# sheet4_sk6812.net
KiCad netlist of a schematic drawn in Altium Designer
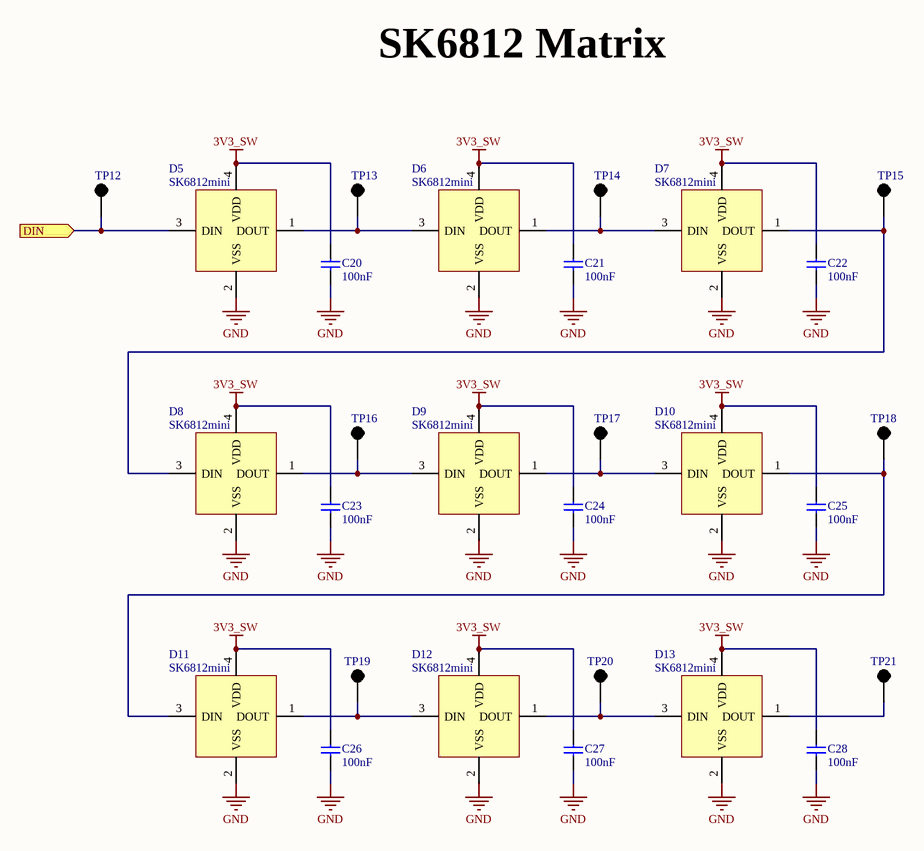
[diagram p0: sheet4_sk6812.SchDoc]

(export (version "E")
  (design (tool "Eeschema 10.0.6"))
  (components
    (comp (ref "C20")
      (value "100nF")
      (footprint "CAP0603_GCx18_MURATA")
      (description "Capacitor 0603 100nF")
      (fields
        (field (name "MANUFACTURER") "Murata")
        (field (name "MANUFACTURER PART NUMBER") "GCJ188R71C104KA01D")
      )
      (libsource (lib "Schlib") (part "CAP_0603_100nF"))
    )
    (comp (ref "C21")
      (value "100nF")
      (footprint "CAP0603_GCx18_MURATA")
      (description "Capacitor 0603 100nF")
      (fields
        (field (name "MANUFACTURER") "Murata")
        (field (name "MANUFACTURER PART NUMBER") "GCJ188R71C104KA01D")
      )
      (libsource (lib "Schlib") (part "CAP_0603_100nF"))
    )
    (comp (ref "C22")
      (value "100nF")
      (footprint "CAP0603_GCx18_MURATA")
      (description "Capacitor 0603 100nF")
      (fields
        (field (name "MANUFACTURER") "Murata")
        (field (name "MANUFACTURER PART NUMBER") "GCJ188R71C104KA01D")
      )
      (libsource (lib "Schlib") (part "CAP_0603_100nF"))
    )
    (comp (ref "C23")
      (value "100nF")
      (footprint "CAP0603_GCx18_MURATA")
      (description "Capacitor 0603 100nF")
      (fields
        (field (name "MANUFACTURER") "Murata")
        (field (name "MANUFACTURER PART NUMBER") "GCJ188R71C104KA01D")
      )
      (libsource (lib "Schlib") (part "CAP_0603_100nF"))
    )
    (comp (ref "C24")
      (value "100nF")
      (footprint "CAP0603_GCx18_MURATA")
      (description "Capacitor 0603 100nF")
      (fields
        (field (name "MANUFACTURER") "Murata")
        (field (name "MANUFACTURER PART NUMBER") "GCJ188R71C104KA01D")
      )
      (libsource (lib "Schlib") (part "CAP_0603_100nF"))
    )
    (comp (ref "C25")
      (value "100nF")
      (footprint "CAP0603_GCx18_MURATA")
      (description "Capacitor 0603 100nF")
      (fields
        (field (name "MANUFACTURER") "Murata")
        (field (name "MANUFACTURER PART NUMBER") "GCJ188R71C104KA01D")
      )
      (libsource (lib "Schlib") (part "CAP_0603_100nF"))
    )
    (comp (ref "C26")
      (value "100nF")
      (footprint "CAP0603_GCx18_MURATA")
      (description "Capacitor 0603 100nF")
      (fields
        (field (name "MANUFACTURER") "Murata")
        (field (name "MANUFACTURER PART NUMBER") "GCJ188R71C104KA01D")
      )
      (libsource (lib "Schlib") (part "CAP_0603_100nF"))
    )
    (comp (ref "C27")
      (value "100nF")
      (footprint "CAP0603_GCx18_MURATA")
      (description "Capacitor 0603 100nF")
      (fields
        (field (name "MANUFACTURER") "Murata")
        (field (name "MANUFACTURER PART NUMBER") "GCJ188R71C104KA01D")
      )
      (libsource (lib "Schlib") (part "CAP_0603_100nF"))
    )
    (comp (ref "C28")
      (value "100nF")
      (footprint "CAP0603_GCx18_MURATA")
      (description "Capacitor 0603 100nF")
      (fields
        (field (name "MANUFACTURER") "Murata")
        (field (name "MANUFACTURER PART NUMBER") "GCJ188R71C104KA01D")
      )
      (libsource (lib "Schlib") (part "CAP_0603_100nF"))
    )
    (comp (ref "D5")
      (value "SK6812mini")
      (footprint "SK6812mini")
      (description "RGB LED with integrated controller")
      (fields (field (name "MANUFACTURER") "Dongguang opsco optoelectronics CO. LTD"))
      (libsource (lib "Schlib") (part "SK6812"))
    )
    (comp (ref "D6")
      (value "SK6812mini")
      (footprint "SK6812mini")
      (description "RGB LED with integrated controller")
      (fields (field (name "MANUFACTURER") "Dongguang opsco optoelectronics CO. LTD"))
      (libsource (lib "Schlib") (part "SK6812"))
    )
    (comp (ref "D7")
      (value "SK6812mini")
      (footprint "SK6812mini")
      (description "RGB LED with integrated controller")
      (fields (field (name "MANUFACTURER") "Dongguang opsco optoelectronics CO. LTD"))
      (libsource (lib "Schlib") (part "SK6812"))
    )
    (comp (ref "D8")
      (value "SK6812mini")
      (footprint "SK6812mini")
      (description "RGB LED with integrated controller")
      (fields (field (name "MANUFACTURER") "Dongguang opsco optoelectronics CO. LTD"))
      (libsource (lib "Schlib") (part "SK6812"))
    )
    (comp (ref "D9")
      (value "SK6812mini")
      (footprint "SK6812mini")
      (description "RGB LED with integrated controller")
      (fields (field (name "MANUFACTURER") "Dongguang opsco optoelectronics CO. LTD"))
      (libsource (lib "Schlib") (part "SK6812"))
    )
    (comp (ref "D10")
      (value "SK6812mini")
      (footprint "SK6812mini")
      (description "RGB LED with integrated controller")
      (fields (field (name "MANUFACTURER") "Dongguang opsco optoelectronics CO. LTD"))
      (libsource (lib "Schlib") (part "SK6812"))
    )
    (comp (ref "D11")
      (value "SK6812mini")
      (footprint "SK6812mini")
      (description "RGB LED with integrated controller")
      (fields (field (name "MANUFACTURER") "Dongguang opsco optoelectronics CO. LTD"))
      (libsource (lib "Schlib") (part "SK6812"))
    )
    (comp (ref "D12")
      (value "SK6812mini")
      (footprint "SK6812mini")
      (description "RGB LED with integrated controller")
      (fields (field (name "MANUFACTURER") "Dongguang opsco optoelectronics CO. LTD"))
      (libsource (lib "Schlib") (part "SK6812"))
    )
    (comp (ref "D13")
      (value "SK6812mini")
      (footprint "SK6812mini")
      (description "RGB LED with integrated controller")
      (fields (field (name "MANUFACTURER") "Dongguang opsco optoelectronics CO. LTD"))
      (libsource (lib "Schlib") (part "SK6812"))
    )
    (comp (ref "TP12")
      (value "testpad")
      (footprint "TestPad")
      (description "Signal probe pad")
      (libsource (lib "Schlib") (part "TestPad"))
    )
    (comp (ref "TP13")
      (value "testpad")
      (footprint "TestPad")
      (description "Signal probe pad")
      (libsource (lib "Schlib") (part "TestPad"))
    )
    (comp (ref "TP14")
      (value "testpad")
      (footprint "TestPad")
      (description "Signal probe pad")
      (libsource (lib "Schlib") (part "TestPad"))
    )
    (comp (ref "TP15")
      (value "testpad")
      (footprint "TestPad")
      (description "Signal probe pad")
      (libsource (lib "Schlib") (part "TestPad"))
    )
    (comp (ref "TP16")
      (value "testpad")
      (footprint "TestPad")
      (description "Signal probe pad")
      (libsource (lib "Schlib") (part "TestPad"))
    )
    (comp (ref "TP17")
      (value "testpad")
      (footprint "TestPad")
      (description "Signal probe pad")
      (libsource (lib "Schlib") (part "TestPad"))
    )
    (comp (ref "TP18")
      (value "testpad")
      (footprint "TestPad")
      (description "Signal probe pad")
      (libsource (lib "Schlib") (part "TestPad"))
    )
    (comp (ref "TP19")
      (value "testpad")
      (footprint "TestPad")
      (description "Signal probe pad")
      (libsource (lib "Schlib") (part "TestPad"))
    )
    (comp (ref "TP20")
      (value "testpad")
      (footprint "TestPad")
      (description "Signal probe pad")
      (libsource (lib "Schlib") (part "TestPad"))
    )
    (comp (ref "TP21")
      (value "testpad")
      (footprint "TestPad")
      (description "Signal probe pad")
      (libsource (lib "Schlib") (part "TestPad"))
    )
  )
  (nets
    (net (code "1") (name "/DIN") (class "Default")
      (node (ref "D5") (pin "3") (pinfunction "DIN_3") (pintype "passive"))
      (node (ref "TP12") (pin "1") (pinfunction "1_1") (pintype "passive"))
    )
    (net (code "2") (name "3V3_SW") (class "Default")
      (node (ref "C20") (pin "2") (pinfunction "2_2") (pintype "passive"))
      (node (ref "C21") (pin "2") (pinfunction "2_2") (pintype "passive"))
      (node (ref "C22") (pin "2") (pinfunction "2_2") (pintype "passive"))
      (node (ref "C23") (pin "2") (pinfunction "2_2") (pintype "passive"))
      (node (ref "C24") (pin "2") (pinfunction "2_2") (pintype "passive"))
      (node (ref "C25") (pin "2") (pinfunction "2_2") (pintype "passive"))
      (node (ref "C26") (pin "2") (pinfunction "2_2") (pintype "passive"))
      (node (ref "C27") (pin "2") (pinfunction "2_2") (pintype "passive"))
      (node (ref "C28") (pin "2") (pinfunction "2_2") (pintype "passive"))
      (node (ref "D10") (pin "4") (pinfunction "VDD_4") (pintype "passive"))
      (node (ref "D11") (pin "4") (pinfunction "VDD_4") (pintype "passive"))
      (node (ref "D12") (pin "4") (pinfunction "VDD_4") (pintype "passive"))
      (node (ref "D13") (pin "4") (pinfunction "VDD_4") (pintype "passive"))
      (node (ref "D5") (pin "4") (pinfunction "VDD_4") (pintype "passive"))
      (node (ref "D6") (pin "4") (pinfunction "VDD_4") (pintype "passive"))
      (node (ref "D7") (pin "4") (pinfunction "VDD_4") (pintype "passive"))
      (node (ref "D8") (pin "4") (pinfunction "VDD_4") (pintype "passive"))
      (node (ref "D9") (pin "4") (pinfunction "VDD_4") (pintype "passive"))
    )
    (net (code "3") (name "GND") (class "Default")
      (node (ref "C20") (pin "1") (pinfunction "1_1") (pintype "passive"))
      (node (ref "C21") (pin "1") (pinfunction "1_1") (pintype "passive"))
      (node (ref "C22") (pin "1") (pinfunction "1_1") (pintype "passive"))
      (node (ref "C23") (pin "1") (pinfunction "1_1") (pintype "passive"))
      (node (ref "C24") (pin "1") (pinfunction "1_1") (pintype "passive"))
      (node (ref "C25") (pin "1") (pinfunction "1_1") (pintype "passive"))
      (node (ref "C26") (pin "1") (pinfunction "1_1") (pintype "passive"))
      (node (ref "C27") (pin "1") (pinfunction "1_1") (pintype "passive"))
      (node (ref "C28") (pin "1") (pinfunction "1_1") (pintype "passive"))
      (node (ref "D10") (pin "2") (pinfunction "VSS_2") (pintype "passive"))
      (node (ref "D11") (pin "2") (pinfunction "VSS_2") (pintype "passive"))
      (node (ref "D12") (pin "2") (pinfunction "VSS_2") (pintype "passive"))
      (node (ref "D13") (pin "2") (pinfunction "VSS_2") (pintype "passive"))
      (node (ref "D5") (pin "2") (pinfunction "VSS_2") (pintype "passive"))
      (node (ref "D6") (pin "2") (pinfunction "VSS_2") (pintype "passive"))
      (node (ref "D7") (pin "2") (pinfunction "VSS_2") (pintype "passive"))
      (node (ref "D8") (pin "2") (pinfunction "VSS_2") (pintype "passive"))
      (node (ref "D9") (pin "2") (pinfunction "VSS_2") (pintype "passive"))
    )
    (net (code "4") (name "Net-(D5-DOUT)") (class "Default")
      (node (ref "D5") (pin "1") (pinfunction "DOUT_1") (pintype "passive"))
      (node (ref "D6") (pin "3") (pinfunction "DIN_3") (pintype "passive"))
      (node (ref "TP13") (pin "1") (pinfunction "1_1") (pintype "passive"))
    )
    (net (code "5") (name "Net-(D6-DOUT)") (class "Default")
      (node (ref "D6") (pin "1") (pinfunction "DOUT_1") (pintype "passive"))
      (node (ref "D7") (pin "3") (pinfunction "DIN_3") (pintype "passive"))
      (node (ref "TP14") (pin "1") (pinfunction "1_1") (pintype "passive"))
    )
    (net (code "6") (name "Net-(D7-DOUT)") (class "Default")
      (node (ref "D7") (pin "1") (pinfunction "DOUT_1") (pintype "passive"))
      (node (ref "D8") (pin "3") (pinfunction "DIN_3") (pintype "passive"))
      (node (ref "TP15") (pin "1") (pinfunction "1_1") (pintype "passive"))
    )
    (net (code "7") (name "Net-(D8-DOUT)") (class "Default")
      (node (ref "D8") (pin "1") (pinfunction "DOUT_1") (pintype "passive"))
      (node (ref "D9") (pin "3") (pinfunction "DIN_3") (pintype "passive"))
      (node (ref "TP16") (pin "1") (pinfunction "1_1") (pintype "passive"))
    )
    (net (code "8") (name "Net-(D10-DIN)") (class "Default")
      (node (ref "D10") (pin "3") (pinfunction "DIN_3") (pintype "passive"))
      (node (ref "D9") (pin "1") (pinfunction "DOUT_1") (pintype "passive"))
      (node (ref "TP17") (pin "1") (pinfunction "1_1") (pintype "passive"))
    )
    (net (code "9") (name "Net-(D10-DOUT)") (class "Default")
      (node (ref "D10") (pin "1") (pinfunction "DOUT_1") (pintype "passive"))
      (node (ref "D11") (pin "3") (pinfunction "DIN_3") (pintype "passive"))
      (node (ref "TP18") (pin "1") (pinfunction "1_1") (pintype "passive"))
    )
    (net (code "10") (name "Net-(D11-DOUT)") (class "Default")
      (node (ref "D11") (pin "1") (pinfunction "DOUT_1") (pintype "passive"))
      (node (ref "D12") (pin "3") (pinfunction "DIN_3") (pintype "passive"))
      (node (ref "TP19") (pin "1") (pinfunction "1_1") (pintype "passive"))
    )
    (net (code "11") (name "Net-(D12-DOUT)") (class "Default")
      (node (ref "D12") (pin "1") (pinfunction "DOUT_1") (pintype "passive"))
      (node (ref "D13") (pin "3") (pinfunction "DIN_3") (pintype "passive"))
      (node (ref "TP20") (pin "1") (pinfunction "1_1") (pintype "passive"))
    )
    (net (code "12") (name "Net-(D13-DOUT)") (class "Default")
      (node (ref "D13") (pin "1") (pinfunction "DOUT_1") (pintype "passive"))
      (node (ref "TP21") (pin "1") (pinfunction "1_1") (pintype "passive"))
    )
  )
)
